# Power.net
KiCad netlist of a schematic drawn in Altium Designer
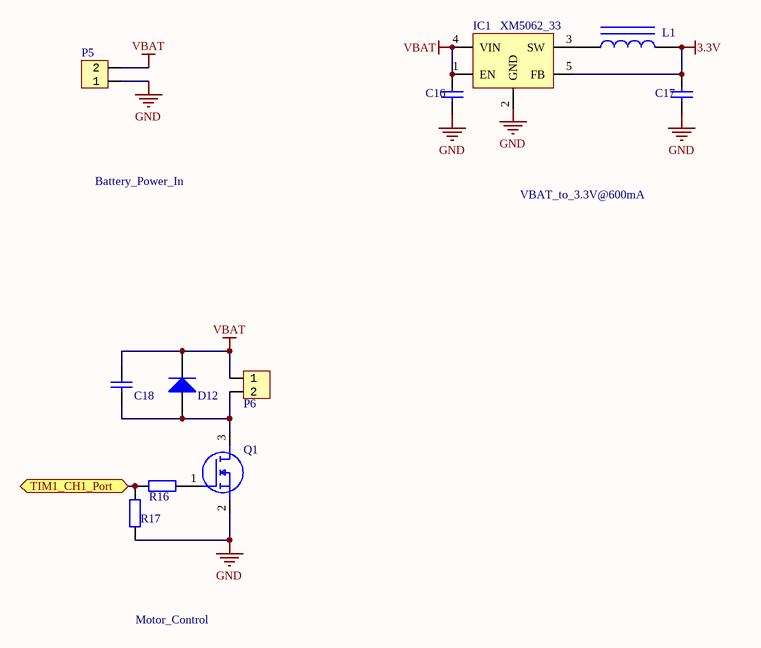
[diagram p0: Power.SchDoc]

(export (version "E")
  (design (tool "Eeschema 10.0.6"))
  (components
    (comp (ref "C16")
      (value "4.7uF")
      (footprint "CAP-0603")
      (description "贴片电容")
      (libsource (lib "Power_Lib_Altium") (part "CAP"))
    )
    (comp (ref "C17")
      (value "10uF")
      (footprint "CAP-0603")
      (description "贴片电容")
      (libsource (lib "Power_Lib_Altium") (part "CAP"))
    )
    (comp (ref "C18")
      (value "10uF")
      (footprint "CAP-0603")
      (description "贴片电容")
      (libsource (lib "Power_Lib_Altium") (part "CAP"))
    )
    (comp (ref "D12")
      (value "SS14")
      (footprint "DO-214AC_SMA")
      (description "二极管")
      (libsource (lib "Power_Lib_Altium") (part "DIODE"))
    )
    (comp (ref "IC1")
      (value "XM5062_33")
      (footprint "SOT-23-5")
      (description "降压转换芯片")
      (fields (field (name "MANUFACTURER_PART_NUMBER") "1-1393258-5"))
      (libsource (lib "Power_Lib_Altium") (part "XM5062"))
    )
    (comp (ref "L1")
      (value "2.2uH")
      (footprint "XAL6060-103MEB")
      (description "贴片电感")
      (libsource (lib "Power_Lib_Altium") (part "INDUCTOR"))
    )
    (comp (ref "P5")
      (value "HDR1x2_2.54")
      (footprint "HDR1X2_2.54_180")
      (description "Header")
      (libsource (lib "") (part "HDR1x2_2.54_1"))
    )
    (comp (ref "P6")
      (value "HDR1x2_2.54")
      (footprint "HDR1X2_2.54_180")
      (description "Header")
      (libsource (lib "Power_Lib_Altium") (part "HDR1x2_2.54"))
    )
    (comp (ref "Q1")
      (value "SI2302DS")
      (footprint "SOT-23-3")
      (description "N 沟道 MOS")
      (fields (field (name "RS PART NUMBER") "7983053P"))
      (libsource (lib "Power_Lib_Altium") (part "N-MOS"))
    )
    (comp (ref "R16")
      (value "22R")
      (footprint "R-0603")
      (description "贴片电阻")
      (libsource (lib "") (part "RES_1"))
    )
    (comp (ref "R17")
      (value "10K")
      (footprint "R-0603")
      (description "贴片电阻")
      (libsource (lib "Power_Lib_Altium") (part "RES"))
    )
  )
  (nets
    (net (code "1") (name "/TIM1_CH1_Port") (class "Default")
      (node (ref "R16") (pin "1") (pinfunction "1_1") (pintype "passive"))
      (node (ref "R17") (pin "2") (pinfunction "2_2") (pintype "passive"))
    )
    (net (code "2") (name "3.3V") (class "Default")
      (node (ref "C17") (pin "2") (pinfunction "2_2") (pintype "passive"))
      (node (ref "IC1") (pin "5") (pinfunction "FB_5") (pintype "passive"))
      (node (ref "L1") (pin "2") (pinfunction "2_2") (pintype "passive"))
    )
    (net (code "3") (name "GND") (class "Default")
      (node (ref "C16") (pin "1") (pinfunction "1_1") (pintype "passive"))
      (node (ref "C17") (pin "1") (pinfunction "1_1") (pintype "passive"))
      (node (ref "IC1") (pin "2") (pinfunction "GND_2") (pintype "passive"))
      (node (ref "P5") (pin "1") (pinfunction "1_1") (pintype "passive"))
      (node (ref "Q1") (pin "2") (pinfunction "S_2") (pintype "passive"))
      (node (ref "R17") (pin "1") (pinfunction "1_1") (pintype "passive"))
    )
    (net (code "4") (name "Net-(D12-A)") (class "Default")
      (node (ref "C18") (pin "1") (pinfunction "1_1") (pintype "passive"))
      (node (ref "D12") (pin "1") (pinfunction "A_1") (pintype "passive"))
      (node (ref "P6") (pin "2") (pinfunction "2_2") (pintype "passive"))
      (node (ref "Q1") (pin "3") (pinfunction "D_3") (pintype "passive"))
    )
    (net (code "5") (name "Net-(IC1-SW)") (class "Default")
      (node (ref "IC1") (pin "3") (pinfunction "SW_3") (pintype "passive"))
      (node (ref "L1") (pin "1") (pinfunction "1_1") (pintype "passive"))
    )
    (net (code "6") (name "Net-(Q1-G)") (class "Default")
      (node (ref "Q1") (pin "1") (pinfunction "G_1") (pintype "passive"))
      (node (ref "R16") (pin "2") (pinfunction "2_2") (pintype "passive"))
    )
    (net (code "7") (name "VBAT") (class "Default")
      (node (ref "C16") (pin "2") (pinfunction "2_2") (pintype "passive"))
      (node (ref "C18") (pin "2") (pinfunction "2_2") (pintype "passive"))
      (node (ref "D12") (pin "2") (pinfunction "K_2") (pintype "passive"))
      (node (ref "IC1") (pin "1") (pinfunction "EN_1") (pintype "passive"))
      (node (ref "IC1") (pin "4") (pinfunction "VIN_4") (pintype "passive"))
      (node (ref "P5") (pin "2") (pinfunction "2_2") (pintype "passive"))
      (node (ref "P6") (pin "1") (pinfunction "1_1") (pintype "passive"))
    )
  )
)
